# untitled-RS485.net
KiCad netlist of a schematic drawn in EAGLE
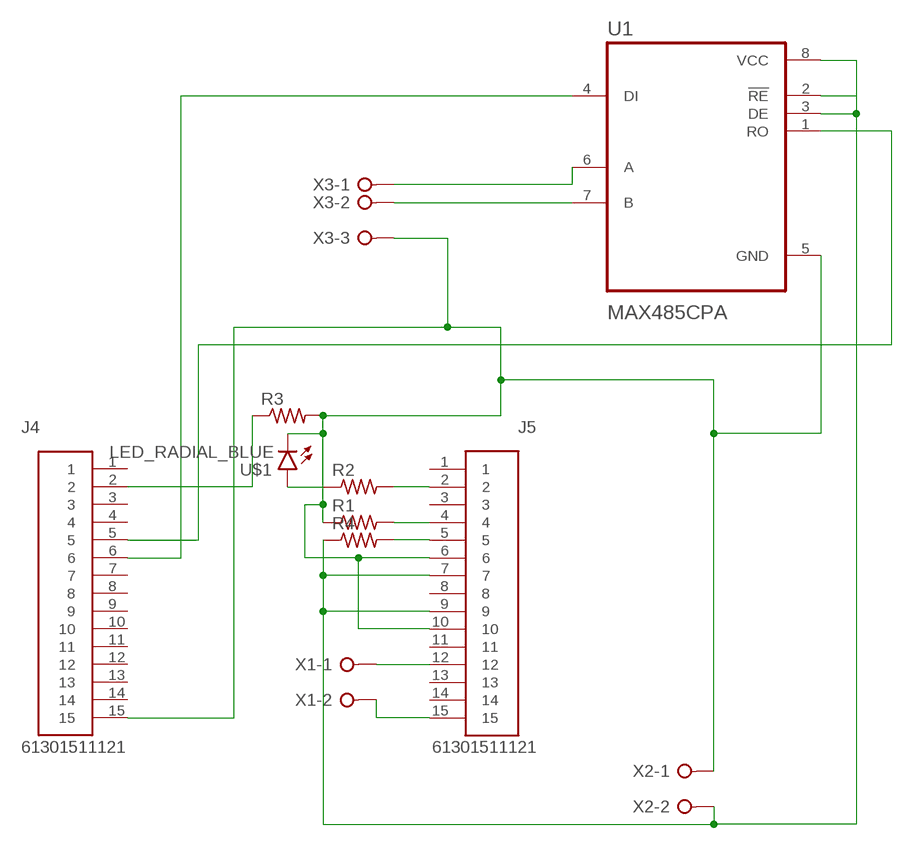
[diagram p0: schematic, sheet 1]

(export (version "E")
  (design (tool "Eeschema 10.0.6"))
  (components
    (comp (ref "J4")
      (value "61301511121")
      (footprint "eagle-import:61301511121")
      (fields
        (field (name "DIGIKEY_PART_NUMBER") "732-5326-ND")
        (field (name "MANUFACTURER") "Wurth Electronics Inc.")
        (field (name "CREATED_BY") "PCBLayout.com")
      )
      (libsource (lib "eagle-import") (part "61301511121"))
    )
    (comp (ref "J5")
      (value "61301511121")
      (footprint "eagle-import:61301511121")
      (fields
        (field (name "DIGIKEY_PART_NUMBER") "732-5326-ND")
        (field (name "MANUFACTURER") "Wurth Electronics Inc.")
        (field (name "CREATED_BY") "PCBLayout.com")
      )
      (libsource (lib "eagle-import") (part "61301511121"))
    )
    (comp (ref "R1")
      (value "R-US_0207/7")
      (footprint "eagle-import:0207_7")
      (libsource (lib "eagle-import") (part "R-US_0207/7"))
    )
    (comp (ref "R2")
      (value "R-US_0207/7")
      (footprint "eagle-import:0207_7")
      (libsource (lib "eagle-import") (part "R-US_0207/7"))
    )
    (comp (ref "R3")
      (value "R-US_0207/7")
      (footprint "eagle-import:0207_7")
      (libsource (lib "eagle-import") (part "R-US_0207/7"))
    )
    (comp (ref "R4")
      (value "R-US_0207/7")
      (footprint "eagle-import:0207_7")
      (libsource (lib "eagle-import") (part "R-US_0207/7"))
    )
    (comp (ref "U$1")
      (value "LED_RADIAL_BLUE")
      (footprint "eagle-import:LEDRD254W60D565H860B_B")
      (libsource (lib "eagle-import") (part "LED_RADIALBLUE_"))
    )
    (comp (ref "U1")
      (value "MAX485CPA")
      (footprint "eagle-import:DIP794W47P254L991H457Q8")
      (fields (field (name "MF") "Maxim Integrated") (field (name "MP") "MAX485CPA+"))
      (libsource (lib "eagle-import") (part "MAX485CPA"))
    )
    (comp (ref "X1")
      (value "W237-02P")
      (footprint "eagle-import:W237-132")
      (libsource (lib "eagle-import") (part "W237-02P"))
    )
    (comp (ref "X2")
      (value "W237-02P")
      (footprint "eagle-import:W237-132")
      (libsource (lib "eagle-import") (part "W237-02P"))
    )
    (comp (ref "X3")
      (value "W237-03P")
      (footprint "eagle-import:W237-133")
      (libsource (lib "eagle-import") (part "W237-03P"))
    )
  )
  (nets
    (net (code "1") (name "Net-(J4-Pad2)") (class "Default")
      (node (ref "J4") (pin "2") (pinfunction "2_2") (pintype "passive"))
      (node (ref "R3") (pin "1") (pinfunction "1_1") (pintype "passive"))
    )
    (net (code "2") (name "Net-(J5-Pad2)") (class "Default")
      (node (ref "J5") (pin "2") (pinfunction "2_2") (pintype "passive"))
      (node (ref "R2") (pin "2") (pinfunction "2_2") (pintype "passive"))
    )
    (net (code "3") (name "Net-(J5-Pad4)") (class "Default")
      (node (ref "J5") (pin "4") (pinfunction "4_4") (pintype "passive"))
      (node (ref "R1") (pin "2") (pinfunction "2_2") (pintype "passive"))
    )
    (net (code "4") (name "Net-(J5-Pad5)") (class "Default")
      (node (ref "J5") (pin "5") (pinfunction "5_5") (pintype "passive"))
      (node (ref "R4") (pin "2") (pinfunction "2_2") (pintype "passive"))
    )
    (net (code "5") (name "Net-(U$1-A)") (class "Default")
      (node (ref "R2") (pin "1") (pinfunction "1_1") (pintype "passive"))
      (node (ref "U$1") (pin "1") (pinfunction "A_1") (pintype "passive"))
    )
    (net (code "6") (name "Net-(U$1-C)") (class "Default")
      (node (ref "J4") (pin "15") (pinfunction "15_15") (pintype "passive"))
      (node (ref "J5") (pin "10") (pinfunction "10_10") (pintype "passive"))
      (node (ref "J5") (pin "6") (pinfunction "6_6") (pintype "passive"))
      (node (ref "R1") (pin "1") (pinfunction "1_1") (pintype "passive"))
      (node (ref "R3") (pin "2") (pinfunction "2_2") (pintype "passive"))
      (node (ref "U$1") (pin "2") (pinfunction "C_2") (pintype "passive"))
      (node (ref "U1") (pin "5") (pinfunction "GND_5") (pintype "power_in"))
      (node (ref "X2") (pin "1") (pinfunction "KL_1") (pintype "passive"))
      (node (ref "X3") (pin "3") (pinfunction "KL_3") (pintype "passive"))
    )
    (net (code "7") (name "Net-(U1-A)") (class "Default")
      (node (ref "U1") (pin "6") (pinfunction "A_6") (pintype "bidirectional"))
      (node (ref "X3") (pin "1") (pinfunction "KL_1") (pintype "passive"))
    )
    (net (code "8") (name "Net-(U1-B)") (class "Default")
      (node (ref "U1") (pin "7") (pinfunction "B_7") (pintype "bidirectional"))
      (node (ref "X3") (pin "2") (pinfunction "KL_2") (pintype "passive"))
    )
    (net (code "9") (name "Net-(U1-DE)") (class "Default")
      (node (ref "J5") (pin "7") (pinfunction "7_7") (pintype "passive"))
      (node (ref "J5") (pin "9") (pinfunction "9_9") (pintype "passive"))
      (node (ref "R4") (pin "1") (pinfunction "1_1") (pintype "passive"))
      (node (ref "U1") (pin "2") (pinfunction "~{RE}_2") (pintype "output"))
      (node (ref "U1") (pin "3") (pinfunction "DE_3") (pintype "output"))
      (node (ref "U1") (pin "8") (pinfunction "VCC_8") (pintype "power_in"))
      (node (ref "X2") (pin "2") (pinfunction "KL_2") (pintype "passive"))
    )
    (net (code "10") (name "Net-(U1-DI)") (class "Default")
      (node (ref "J4") (pin "6") (pinfunction "6_6") (pintype "passive"))
      (node (ref "U1") (pin "4") (pinfunction "DI_4") (pintype "input"))
    )
    (net (code "11") (name "Net-(U1-RO)") (class "Default")
      (node (ref "J4") (pin "5") (pinfunction "5_5") (pintype "passive"))
      (node (ref "U1") (pin "1") (pinfunction "RO_1") (pintype "output"))
    )
    (net (code "12") (name "Net-(X1A-KL)") (class "Default")
      (node (ref "J5") (pin "12") (pinfunction "12_12") (pintype "passive"))
      (node (ref "X1") (pin "1") (pinfunction "KL_1") (pintype "passive"))
    )
    (net (code "13") (name "Net-(X1B-KL)") (class "Default")
      (node (ref "J5") (pin "15") (pinfunction "15_15") (pintype "passive"))
      (node (ref "X1") (pin "2") (pinfunction "KL_2") (pintype "passive"))
    )
    (net (code "14") (name "unconnected-(J4-Pad1)") (class "Default")
      (node (ref "J4") (pin "1") (pinfunction "1_1") (pintype "passive"))
    )
    (net (code "15") (name "unconnected-(J4-Pad3)") (class "Default")
      (node (ref "J4") (pin "3") (pinfunction "3_3") (pintype "passive"))
    )
    (net (code "16") (name "unconnected-(J4-Pad4)") (class "Default")
      (node (ref "J4") (pin "4") (pinfunction "4_4") (pintype "passive"))
    )
    (net (code "17") (name "unconnected-(J4-Pad7)") (class "Default")
      (node (ref "J4") (pin "7") (pinfunction "7_7") (pintype "passive"))
    )
    (net (code "18") (name "unconnected-(J4-Pad8)") (class "Default")
      (node (ref "J4") (pin "8") (pinfunction "8_8") (pintype "passive"))
    )
    (net (code "19") (name "unconnected-(J4-Pad9)") (class "Default")
      (node (ref "J4") (pin "9") (pinfunction "9_9") (pintype "passive"))
    )
    (net (code "20") (name "unconnected-(J4-Pad10)") (class "Default")
      (node (ref "J4") (pin "10") (pinfunction "10_10") (pintype "passive"))
    )
    (net (code "21") (name "unconnected-(J4-Pad11)") (class "Default")
      (node (ref "J4") (pin "11") (pinfunction "11_11") (pintype "passive"))
    )
    (net (code "22") (name "unconnected-(J4-Pad12)") (class "Default")
      (node (ref "J4") (pin "12") (pinfunction "12_12") (pintype "passive"))
    )
    (net (code "23") (name "unconnected-(J4-Pad13)") (class "Default")
      (node (ref "J4") (pin "13") (pinfunction "13_13") (pintype "passive"))
    )
    (net (code "24") (name "unconnected-(J4-Pad14)") (class "Default")
      (node (ref "J4") (pin "14") (pinfunction "14_14") (pintype "passive"))
    )
    (net (code "25") (name "unconnected-(J5-Pad1)") (class "Default")
      (node (ref "J5") (pin "1") (pinfunction "1_1") (pintype "passive"))
    )
    (net (code "26") (name "unconnected-(J5-Pad3)") (class "Default")
      (node (ref "J5") (pin "3") (pinfunction "3_3") (pintype "passive"))
    )
    (net (code "27") (name "unconnected-(J5-Pad8)") (class "Default")
      (node (ref "J5") (pin "8") (pinfunction "8_8") (pintype "passive"))
    )
    (net (code "28") (name "unconnected-(J5-Pad11)") (class "Default")
      (node (ref "J5") (pin "11") (pinfunction "11_11") (pintype "passive"))
    )
    (net (code "29") (name "unconnected-(J5-Pad13)") (class "Default")
      (node (ref "J5") (pin "13") (pinfunction "13_13") (pintype "passive"))
    )
    (net (code "30") (name "unconnected-(J5-Pad14)") (class "Default")
      (node (ref "J5") (pin "14") (pinfunction "14_14") (pintype "passive"))
    )
  )
)
